# cnc-data-panel.net
KiCad netlist of a schematic drawn in EAGLE
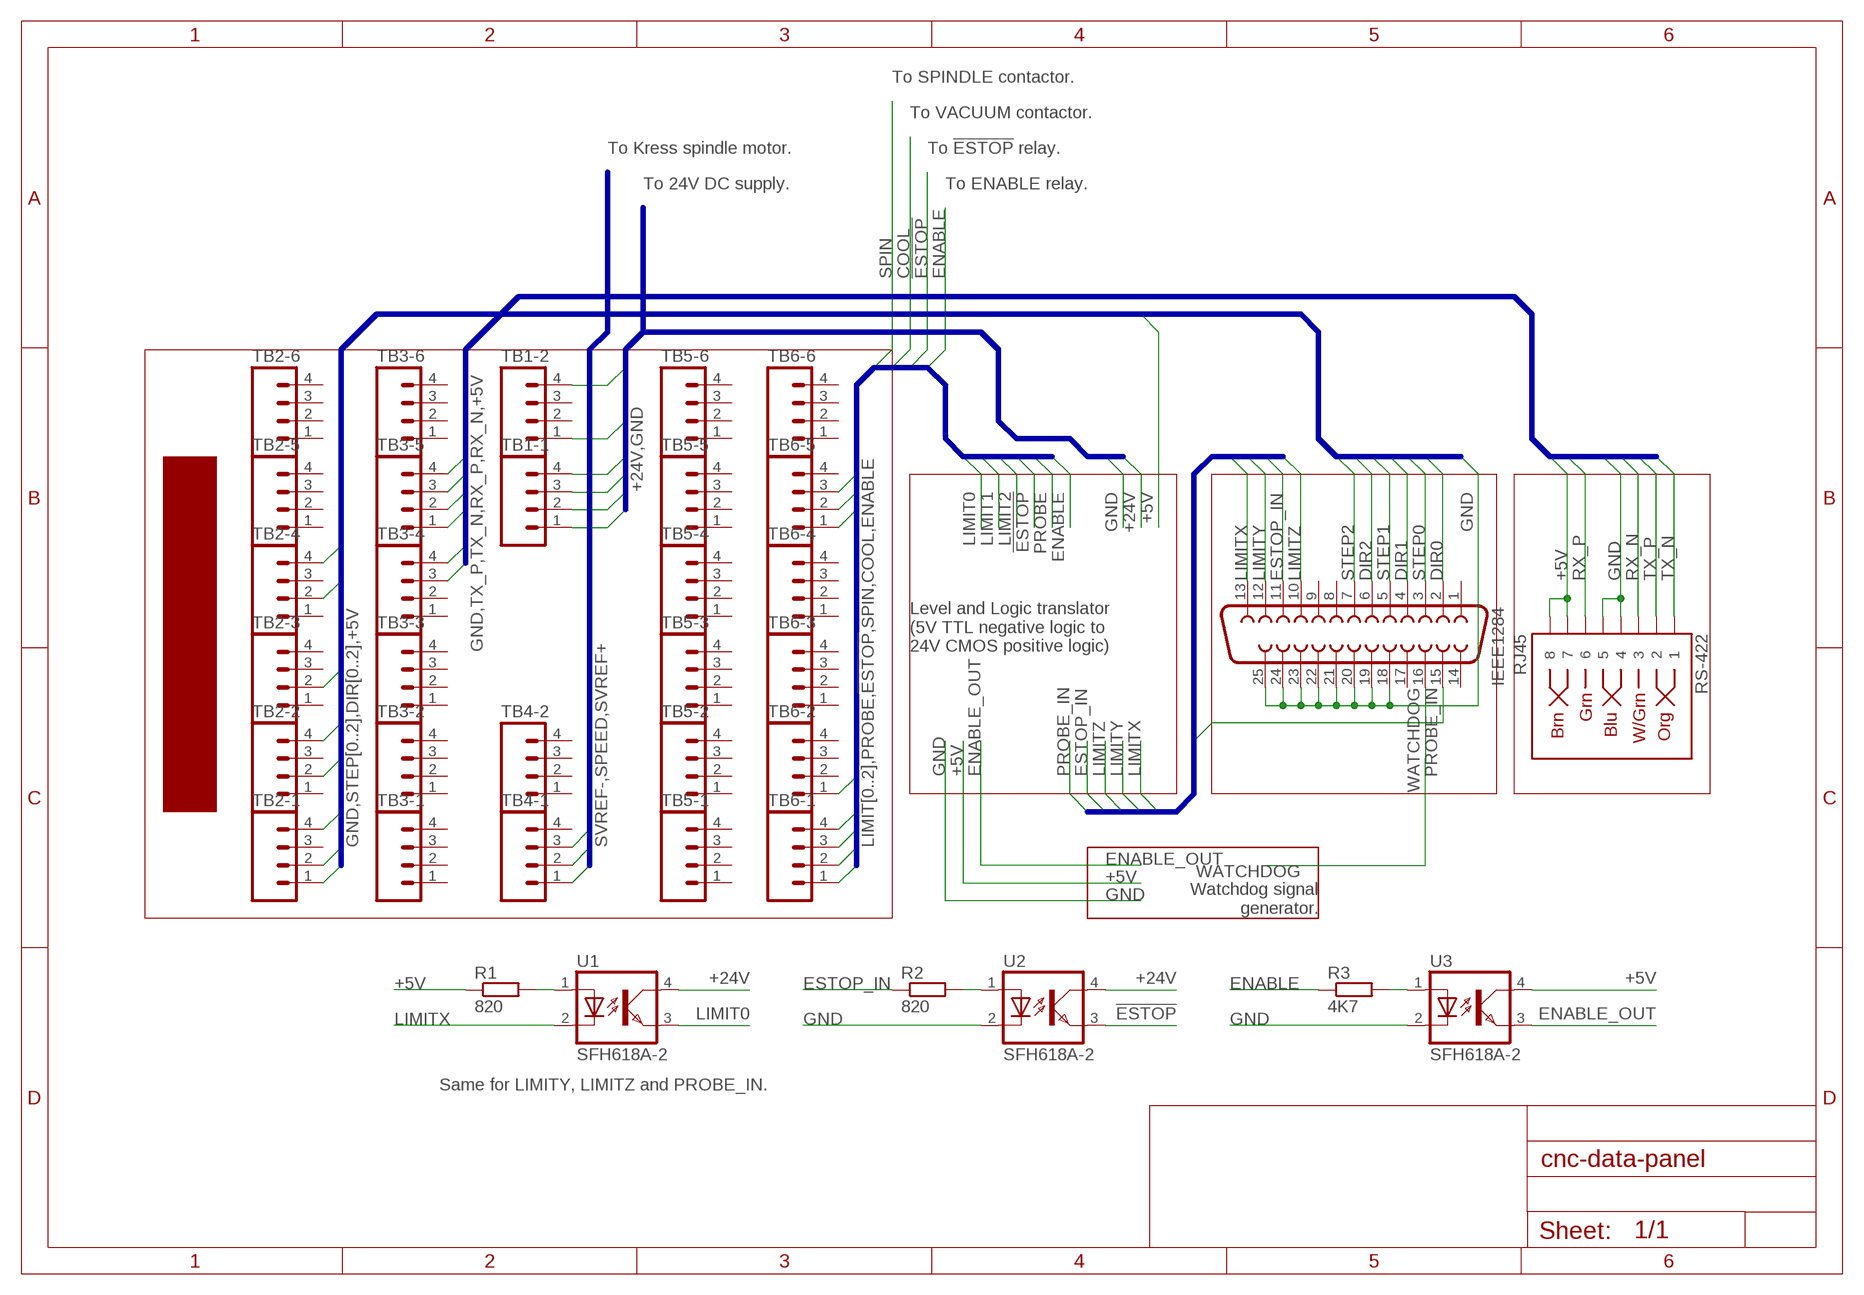
[diagram p0: schematic, sheet 1]

(export (version "E")
  (design (tool "Eeschema 10.0.6"))
  (components
    (comp (ref "IEEE1284")
      (value "F25VP")
      (footprint "eagle-import:F25VP")
      (libsource (lib "eagle-import") (part "F25VP"))
    )
    (comp (ref "R1")
      (value "820")
      (footprint "eagle-import:0204V")
      (libsource (lib "eagle-import") (part "R-EU_0204/2V"))
    )
    (comp (ref "R2")
      (value "820")
      (footprint "eagle-import:0204V")
      (libsource (lib "eagle-import") (part "R-EU_0204/2V"))
    )
    (comp (ref "R3")
      (value "4K7")
      (footprint "eagle-import:0204V")
      (libsource (lib "eagle-import") (part "R-EU_0204/2V"))
    )
    (comp (ref "RS-422")
      (value "RJ45")
      (footprint "eagle-import:RJ45-8")
      (libsource (lib "eagle-import") (part "RJ45-8PTH"))
    )
    (comp (ref "TB1-1")
      (value "M04SCREW")
      (footprint "eagle-import:SCREWTERMINAL-3.5MM-4")
      (libsource (lib "eagle-import") (part "M04SCREW"))
    )
    (comp (ref "TB1-2")
      (value "M04SCREW")
      (footprint "eagle-import:SCREWTERMINAL-3.5MM-4")
      (libsource (lib "eagle-import") (part "M04SCREW"))
    )
    (comp (ref "TB2-1")
      (value "M04SCREW")
      (footprint "eagle-import:SCREWTERMINAL-3.5MM-4")
      (libsource (lib "eagle-import") (part "M04SCREW"))
    )
    (comp (ref "TB2-2")
      (value "M04SCREW")
      (footprint "eagle-import:SCREWTERMINAL-3.5MM-4")
      (libsource (lib "eagle-import") (part "M04SCREW"))
    )
    (comp (ref "TB2-3")
      (value "M04SCREW")
      (footprint "eagle-import:SCREWTERMINAL-3.5MM-4")
      (libsource (lib "eagle-import") (part "M04SCREW"))
    )
    (comp (ref "TB2-4")
      (value "M04SCREW")
      (footprint "eagle-import:SCREWTERMINAL-3.5MM-4")
      (libsource (lib "eagle-import") (part "M04SCREW"))
    )
    (comp (ref "TB2-5")
      (value "M04SCREW")
      (footprint "eagle-import:SCREWTERMINAL-3.5MM-4")
      (libsource (lib "eagle-import") (part "M04SCREW"))
    )
    (comp (ref "TB2-6")
      (value "M04SCREW")
      (footprint "eagle-import:SCREWTERMINAL-3.5MM-4")
      (libsource (lib "eagle-import") (part "M04SCREW"))
    )
    (comp (ref "TB3-1")
      (value "M04SCREW")
      (footprint "eagle-import:SCREWTERMINAL-3.5MM-4")
      (libsource (lib "eagle-import") (part "M04SCREW"))
    )
    (comp (ref "TB3-2")
      (value "M04SCREW")
      (footprint "eagle-import:SCREWTERMINAL-3.5MM-4")
      (libsource (lib "eagle-import") (part "M04SCREW"))
    )
    (comp (ref "TB3-3")
      (value "M04SCREW")
      (footprint "eagle-import:SCREWTERMINAL-3.5MM-4")
      (libsource (lib "eagle-import") (part "M04SCREW"))
    )
    (comp (ref "TB3-4")
      (value "M04SCREW")
      (footprint "eagle-import:SCREWTERMINAL-3.5MM-4")
      (libsource (lib "eagle-import") (part "M04SCREW"))
    )
    (comp (ref "TB3-5")
      (value "M04SCREW")
      (footprint "eagle-import:SCREWTERMINAL-3.5MM-4")
      (libsource (lib "eagle-import") (part "M04SCREW"))
    )
    (comp (ref "TB3-6")
      (value "M04SCREW")
      (footprint "eagle-import:SCREWTERMINAL-3.5MM-4")
      (libsource (lib "eagle-import") (part "M04SCREW"))
    )
    (comp (ref "TB4-1")
      (value "M04SCREW")
      (footprint "eagle-import:SCREWTERMINAL-3.5MM-4")
      (libsource (lib "eagle-import") (part "M04SCREW"))
    )
    (comp (ref "TB4-2")
      (value "M04SCREW")
      (footprint "eagle-import:SCREWTERMINAL-3.5MM-4")
      (libsource (lib "eagle-import") (part "M04SCREW"))
    )
    (comp (ref "TB5-1")
      (value "M04SCREW")
      (footprint "eagle-import:SCREWTERMINAL-3.5MM-4")
      (libsource (lib "eagle-import") (part "M04SCREW"))
    )
    (comp (ref "TB5-2")
      (value "M04SCREW")
      (footprint "eagle-import:SCREWTERMINAL-3.5MM-4")
      (libsource (lib "eagle-import") (part "M04SCREW"))
    )
    (comp (ref "TB5-3")
      (value "M04SCREW")
      (footprint "eagle-import:SCREWTERMINAL-3.5MM-4")
      (libsource (lib "eagle-import") (part "M04SCREW"))
    )
    (comp (ref "TB5-4")
      (value "M04SCREW")
      (footprint "eagle-import:SCREWTERMINAL-3.5MM-4")
      (libsource (lib "eagle-import") (part "M04SCREW"))
    )
    (comp (ref "TB5-5")
      (value "M04SCREW")
      (footprint "eagle-import:SCREWTERMINAL-3.5MM-4")
      (libsource (lib "eagle-import") (part "M04SCREW"))
    )
    (comp (ref "TB5-6")
      (value "M04SCREW")
      (footprint "eagle-import:SCREWTERMINAL-3.5MM-4")
      (libsource (lib "eagle-import") (part "M04SCREW"))
    )
    (comp (ref "TB6-1")
      (value "M04SCREW")
      (footprint "eagle-import:SCREWTERMINAL-3.5MM-4")
      (libsource (lib "eagle-import") (part "M04SCREW"))
    )
    (comp (ref "TB6-2")
      (value "M04SCREW")
      (footprint "eagle-import:SCREWTERMINAL-3.5MM-4")
      (libsource (lib "eagle-import") (part "M04SCREW"))
    )
    (comp (ref "TB6-3")
      (value "M04SCREW")
      (footprint "eagle-import:SCREWTERMINAL-3.5MM-4")
      (libsource (lib "eagle-import") (part "M04SCREW"))
    )
    (comp (ref "TB6-4")
      (value "M04SCREW")
      (footprint "eagle-import:SCREWTERMINAL-3.5MM-4")
      (libsource (lib "eagle-import") (part "M04SCREW"))
    )
    (comp (ref "TB6-5")
      (value "M04SCREW")
      (footprint "eagle-import:SCREWTERMINAL-3.5MM-4")
      (libsource (lib "eagle-import") (part "M04SCREW"))
    )
    (comp (ref "TB6-6")
      (value "M04SCREW")
      (footprint "eagle-import:SCREWTERMINAL-3.5MM-4")
      (libsource (lib "eagle-import") (part "M04SCREW"))
    )
    (comp (ref "U1")
      (value "SFH618A-2")
      (footprint "eagle-import:DIP4")
      (fields (field (name "MF") "VISHAY/TELEFUNKEN"))
      (libsource (lib "eagle-import") (part "SFH618?A-2"))
    )
    (comp (ref "U2")
      (value "SFH618A-2")
      (footprint "eagle-import:DIP4")
      (fields (field (name "MF") "VISHAY/TELEFUNKEN"))
      (libsource (lib "eagle-import") (part "SFH618?A-2"))
    )
    (comp (ref "U3")
      (value "SFH618A-2")
      (footprint "eagle-import:DIP4")
      (fields (field (name "MF") "VISHAY/TELEFUNKEN"))
      (libsource (lib "eagle-import") (part "SFH618?A-2"))
    )
  )
  (nets
    (net (code "4") (name "/+5V") (class "Default")
      (node (ref "R1") (pin "1") (pinfunction "1_1") (pintype "passive"))
      (node (ref "RS-422") (pin "7") (pinfunction "7_7") (pintype "bidirectional"))
      (node (ref "RS-422") (pin "8") (pinfunction "8_8") (pintype "bidirectional"))
      (node (ref "TB2-2") (pin "2") (pinfunction "2_2") (pintype "passive"))
      (node (ref "TB3-5") (pin "4") (pinfunction "4_4") (pintype "passive"))
      (node (ref "U3") (pin "4") (pinfunction "COL_4") (pintype "passive"))
    )
    (net (code "5") (name "/+24V") (class "Default")
      (node (ref "TB1-1") (pin "1") (pinfunction "1_1") (pintype "passive"))
      (node (ref "TB1-1") (pin "2") (pinfunction "2_2") (pintype "passive"))
      (node (ref "TB1-1") (pin "3") (pinfunction "3_3") (pintype "passive"))
      (node (ref "TB1-1") (pin "4") (pinfunction "4_4") (pintype "passive"))
      (node (ref "TB1-2") (pin "1") (pinfunction "1_1") (pintype "passive"))
      (node (ref "U1") (pin "4") (pinfunction "COL_4") (pintype "passive"))
      (node (ref "U2") (pin "4") (pinfunction "COL_4") (pintype "passive"))
    )
    (net (code "6") (name "/COOL") (class "Default")
      (node (ref "TB6-5") (pin "2") (pinfunction "2_2") (pintype "passive"))
    )
    (net (code "7") (name "/DIR0") (class "Default")
      (node (ref "IEEE1284") (pin "2") (pinfunction "2_2") (pintype "passive"))
      (node (ref "TB2-1") (pin "4") (pinfunction "4_4") (pintype "passive"))
    )
    (net (code "8") (name "/DIR1") (class "Default")
      (node (ref "IEEE1284") (pin "4") (pinfunction "4_4") (pintype "passive"))
      (node (ref "TB2-3") (pin "2") (pinfunction "2_2") (pintype "passive"))
    )
    (net (code "9") (name "/DIR2") (class "Default")
      (node (ref "IEEE1284") (pin "6") (pinfunction "6_6") (pintype "passive"))
      (node (ref "TB2-4") (pin "4") (pinfunction "4_4") (pintype "passive"))
    )
    (net (code "10") (name "/ENABLE") (class "Default")
      (node (ref "R3") (pin "1") (pinfunction "1_1") (pintype "passive"))
      (node (ref "TB6-5") (pin "3") (pinfunction "3_3") (pintype "passive"))
    )
    (net (code "11") (name "/ENABLE_OUT") (class "Default")
      (node (ref "U3") (pin "3") (pinfunction "EMIT_3") (pintype "passive"))
    )
    (net (code "12") (name "/ESTOP_IN") (class "Default")
      (node (ref "IEEE1284") (pin "11") (pinfunction "11_11") (pintype "passive"))
      (node (ref "R2") (pin "1") (pinfunction "1_1") (pintype "passive"))
    )
    (net (code "13") (name "/GND") (class "Default")
      (node (ref "IEEE1284") (pin "18") (pinfunction "18_18") (pintype "passive"))
      (node (ref "IEEE1284") (pin "19") (pinfunction "19_19") (pintype "passive"))
      (node (ref "IEEE1284") (pin "20") (pinfunction "20_20") (pintype "passive"))
      (node (ref "IEEE1284") (pin "21") (pinfunction "21_21") (pintype "passive"))
      (node (ref "IEEE1284") (pin "22") (pinfunction "22_22") (pintype "passive"))
      (node (ref "IEEE1284") (pin "23") (pinfunction "23_23") (pintype "passive"))
      (node (ref "IEEE1284") (pin "24") (pinfunction "24_24") (pintype "passive"))
      (node (ref "IEEE1284") (pin "25") (pinfunction "25_25") (pintype "passive"))
      (node (ref "RS-422") (pin "4") (pinfunction "4_4") (pintype "bidirectional"))
      (node (ref "RS-422") (pin "5") (pinfunction "5_5") (pintype "bidirectional"))
      (node (ref "TB1-2") (pin "4") (pinfunction "4_4") (pintype "passive"))
      (node (ref "TB2-1") (pin "1") (pinfunction "1_1") (pintype "passive"))
      (node (ref "TB3-4") (pin "3") (pinfunction "3_3") (pintype "passive"))
      (node (ref "U2") (pin "2") (pinfunction "C_2") (pintype "passive"))
      (node (ref "U3") (pin "2") (pinfunction "C_2") (pintype "passive"))
    )
    (net (code "14") (name "/LIMIT0") (class "Default")
      (node (ref "TB6-1") (pin "1") (pinfunction "1_1") (pintype "passive"))
      (node (ref "U1") (pin "3") (pinfunction "EMIT_3") (pintype "passive"))
    )
    (net (code "15") (name "/LIMIT1") (class "Default")
      (node (ref "TB6-1") (pin "2") (pinfunction "2_2") (pintype "passive"))
    )
    (net (code "16") (name "/LIMIT2") (class "Default")
      (node (ref "TB6-1") (pin "3") (pinfunction "3_3") (pintype "passive"))
    )
    (net (code "17") (name "/LIMITX") (class "Default")
      (node (ref "IEEE1284") (pin "13") (pinfunction "13_13") (pintype "passive"))
      (node (ref "U1") (pin "2") (pinfunction "C_2") (pintype "passive"))
    )
    (net (code "18") (name "/LIMITY") (class "Default")
      (node (ref "IEEE1284") (pin "12") (pinfunction "12_12") (pintype "passive"))
    )
    (net (code "19") (name "/LIMITZ") (class "Default")
      (node (ref "IEEE1284") (pin "10") (pinfunction "10_10") (pintype "passive"))
    )
    (net (code "20") (name "/PROBE") (class "Default")
      (node (ref "TB6-1") (pin "4") (pinfunction "4_4") (pintype "passive"))
    )
    (net (code "21") (name "/PROBE_IN") (class "Default")
      (node (ref "IEEE1284") (pin "15") (pinfunction "15_15") (pintype "passive"))
    )
    (net (code "22") (name "/RX_N") (class "Default")
      (node (ref "RS-422") (pin "3") (pinfunction "3_3") (pintype "bidirectional"))
      (node (ref "TB3-5") (pin "1") (pinfunction "1_1") (pintype "passive"))
    )
    (net (code "23") (name "/RX_P") (class "Default")
      (node (ref "RS-422") (pin "6") (pinfunction "6_6") (pintype "bidirectional"))
      (node (ref "TB3-4") (pin "4") (pinfunction "4_4") (pintype "passive"))
    )
    (net (code "24") (name "/SPIN") (class "Default")
      (node (ref "TB6-5") (pin "1") (pinfunction "1_1") (pintype "passive"))
    )
    (net (code "25") (name "/STEP0") (class "Default")
      (node (ref "IEEE1284") (pin "3") (pinfunction "3_3") (pintype "passive"))
      (node (ref "TB2-1") (pin "2") (pinfunction "2_2") (pintype "passive"))
    )
    (net (code "26") (name "/STEP1") (class "Default")
      (node (ref "IEEE1284") (pin "5") (pinfunction "5_5") (pintype "passive"))
      (node (ref "TB2-2") (pin "4") (pinfunction "4_4") (pintype "passive"))
    )
    (net (code "27") (name "/STEP2") (class "Default")
      (node (ref "IEEE1284") (pin "7") (pinfunction "7_7") (pintype "passive"))
      (node (ref "TB2-4") (pin "2") (pinfunction "2_2") (pintype "passive"))
    )
    (net (code "28") (name "/TX_N") (class "Default")
      (node (ref "RS-422") (pin "1") (pinfunction "1_1") (pintype "bidirectional"))
      (node (ref "TB3-5") (pin "3") (pinfunction "3_3") (pintype "passive"))
    )
    (net (code "29") (name "/TX_P") (class "Default")
      (node (ref "RS-422") (pin "2") (pinfunction "2_2") (pintype "bidirectional"))
      (node (ref "TB3-5") (pin "2") (pinfunction "2_2") (pintype "passive"))
    )
    (net (code "30") (name "/WATCHDOG") (class "Default")
      (node (ref "IEEE1284") (pin "16") (pinfunction "16_16") (pintype "passive"))
    )
    (net (code "36") (name "/~{ESTOP}") (class "Default")
      (node (ref "TB6-2") (pin "1") (pinfunction "1_1") (pintype "passive"))
      (node (ref "U2") (pin "3") (pinfunction "EMIT_3") (pintype "passive"))
    )
    (net (code "37") (name "Net-(U1-A)") (class "Default")
      (node (ref "R1") (pin "2") (pinfunction "2_2") (pintype "passive"))
      (node (ref "U1") (pin "1") (pinfunction "A_1") (pintype "passive"))
    )
    (net (code "38") (name "Net-(U2-A)") (class "Default")
      (node (ref "R2") (pin "2") (pinfunction "2_2") (pintype "passive"))
      (node (ref "U2") (pin "1") (pinfunction "A_1") (pintype "passive"))
    )
    (net (code "39") (name "Net-(U3-A)") (class "Default")
      (node (ref "R3") (pin "2") (pinfunction "2_2") (pintype "passive"))
      (node (ref "U3") (pin "1") (pinfunction "A_1") (pintype "passive"))
    )
    (net (code "40") (name "unconnected-(IEEE1284-Pad1)") (class "Default")
      (node (ref "IEEE1284") (pin "1") (pinfunction "1_1") (pintype "passive"))
    )
    (net (code "41") (name "unconnected-(IEEE1284-Pad8)") (class "Default")
      (node (ref "IEEE1284") (pin "8") (pinfunction "8_8") (pintype "passive"))
    )
    (net (code "42") (name "unconnected-(IEEE1284-Pad9)") (class "Default")
      (node (ref "IEEE1284") (pin "9") (pinfunction "9_9") (pintype "passive"))
    )
    (net (code "43") (name "unconnected-(IEEE1284-Pad14)") (class "Default")
      (node (ref "IEEE1284") (pin "14") (pinfunction "14_14") (pintype "passive"))
    )
    (net (code "44") (name "unconnected-(IEEE1284-Pad17)") (class "Default")
      (node (ref "IEEE1284") (pin "17") (pinfunction "17_17") (pintype "passive"))
    )
    (net (code "45") (name "unconnected-(TB1-2-Pad2)") (class "Default")
      (node (ref "TB1-2") (pin "2") (pinfunction "2_2") (pintype "passive"))
    )
    (net (code "46") (name "unconnected-(TB1-2-Pad3)") (class "Default")
      (node (ref "TB1-2") (pin "3") (pinfunction "3_3") (pintype "passive"))
    )
    (net (code "47") (name "unconnected-(TB2-1-Pad3)") (class "Default")
      (node (ref "TB2-1") (pin "3") (pinfunction "3_3") (pintype "passive"))
    )
    (net (code "48") (name "unconnected-(TB2-2-Pad1)") (class "Default")
      (node (ref "TB2-2") (pin "1") (pinfunction "1_1") (pintype "passive"))
    )
    (net (code "49") (name "unconnected-(TB2-2-Pad3)") (class "Default")
      (node (ref "TB2-2") (pin "3") (pinfunction "3_3") (pintype "passive"))
    )
    (net (code "50") (name "unconnected-(TB2-3-Pad1)") (class "Default")
      (node (ref "TB2-3") (pin "1") (pinfunction "1_1") (pintype "passive"))
    )
    (net (code "51") (name "unconnected-(TB2-3-Pad3)") (class "Default")
      (node (ref "TB2-3") (pin "3") (pinfunction "3_3") (pintype "passive"))
    )
    (net (code "52") (name "unconnected-(TB2-3-Pad4)") (class "Default")
      (node (ref "TB2-3") (pin "4") (pinfunction "4_4") (pintype "passive"))
    )
    (net (code "53") (name "unconnected-(TB2-4-Pad1)") (class "Default")
      (node (ref "TB2-4") (pin "1") (pinfunction "1_1") (pintype "passive"))
    )
    (net (code "54") (name "unconnected-(TB2-4-Pad3)") (class "Default")
      (node (ref "TB2-4") (pin "3") (pinfunction "3_3") (pintype "passive"))
    )
    (net (code "55") (name "unconnected-(TB2-5-Pad1)") (class "Default")
      (node (ref "TB2-5") (pin "1") (pinfunction "1_1") (pintype "passive"))
    )
    (net (code "56") (name "unconnected-(TB2-5-Pad2)") (class "Default")
      (node (ref "TB2-5") (pin "2") (pinfunction "2_2") (pintype "passive"))
    )
    (net (code "57") (name "unconnected-(TB2-5-Pad3)") (class "Default")
      (node (ref "TB2-5") (pin "3") (pinfunction "3_3") (pintype "passive"))
    )
    (net (code "58") (name "unconnected-(TB2-5-Pad4)") (class "Default")
      (node (ref "TB2-5") (pin "4") (pinfunction "4_4") (pintype "passive"))
    )
    (net (code "59") (name "unconnected-(TB2-6-Pad1)") (class "Default")
      (node (ref "TB2-6") (pin "1") (pinfunction "1_1") (pintype "passive"))
    )
    (net (code "60") (name "unconnected-(TB2-6-Pad2)") (class "Default")
      (node (ref "TB2-6") (pin "2") (pinfunction "2_2") (pintype "passive"))
    )
    (net (code "61") (name "unconnected-(TB2-6-Pad3)") (class "Default")
      (node (ref "TB2-6") (pin "3") (pinfunction "3_3") (pintype "passive"))
    )
    (net (code "62") (name "unconnected-(TB2-6-Pad4)") (class "Default")
      (node (ref "TB2-6") (pin "4") (pinfunction "4_4") (pintype "passive"))
    )
    (net (code "63") (name "unconnected-(TB3-1-Pad1)") (class "Default")
      (node (ref "TB3-1") (pin "1") (pinfunction "1_1") (pintype "passive"))
    )
    (net (code "64") (name "unconnected-(TB3-1-Pad2)") (class "Default")
      (node (ref "TB3-1") (pin "2") (pinfunction "2_2") (pintype "passive"))
    )
    (net (code "65") (name "unconnected-(TB3-1-Pad3)") (class "Default")
      (node (ref "TB3-1") (pin "3") (pinfunction "3_3") (pintype "passive"))
    )
    (net (code "66") (name "unconnected-(TB3-1-Pad4)") (class "Default")
      (node (ref "TB3-1") (pin "4") (pinfunction "4_4") (pintype "passive"))
    )
    (net (code "67") (name "unconnected-(TB3-2-Pad1)") (class "Default")
      (node (ref "TB3-2") (pin "1") (pinfunction "1_1") (pintype "passive"))
    )
    (net (code "68") (name "unconnected-(TB3-2-Pad2)") (class "Default")
      (node (ref "TB3-2") (pin "2") (pinfunction "2_2") (pintype "passive"))
    )
    (net (code "69") (name "unconnected-(TB3-2-Pad3)") (class "Default")
      (node (ref "TB3-2") (pin "3") (pinfunction "3_3") (pintype "passive"))
    )
    (net (code "70") (name "unconnected-(TB3-2-Pad4)") (class "Default")
      (node (ref "TB3-2") (pin "4") (pinfunction "4_4") (pintype "passive"))
    )
    (net (code "71") (name "unconnected-(TB3-3-Pad1)") (class "Default")
      (node (ref "TB3-3") (pin "1") (pinfunction "1_1") (pintype "passive"))
    )
    (net (code "72") (name "unconnected-(TB3-3-Pad2)") (class "Default")
      (node (ref "TB3-3") (pin "2") (pinfunction "2_2") (pintype "passive"))
    )
    (net (code "73") (name "unconnected-(TB3-3-Pad3)") (class "Default")
      (node (ref "TB3-3") (pin "3") (pinfunction "3_3") (pintype "passive"))
    )
    (net (code "74") (name "unconnected-(TB3-3-Pad4)") (class "Default")
      (node (ref "TB3-3") (pin "4") (pinfunction "4_4") (pintype "passive"))
    )
    (net (code "75") (name "unconnected-(TB3-4-Pad1)") (class "Default")
      (node (ref "TB3-4") (pin "1") (pinfunction "1_1") (pintype "passive"))
    )
    (net (code "76") (name "unconnected-(TB3-4-Pad2)") (class "Default")
      (node (ref "TB3-4") (pin "2") (pinfunction "2_2") (pintype "passive"))
    )
    (net (code "77") (name "unconnected-(TB3-6-Pad1)") (class "Default")
      (node (ref "TB3-6") (pin "1") (pinfunction "1_1") (pintype "passive"))
    )
    (net (code "78") (name "unconnected-(TB3-6-Pad2)") (class "Default")
      (node (ref "TB3-6") (pin "2") (pinfunction "2_2") (pintype "passive"))
    )
    (net (code "79") (name "unconnected-(TB3-6-Pad3)") (class "Default")
      (node (ref "TB3-6") (pin "3") (pinfunction "3_3") (pintype "passive"))
    )
    (net (code "80") (name "unconnected-(TB3-6-Pad4)") (class "Default")
      (node (ref "TB3-6") (pin "4") (pinfunction "4_4") (pintype "passive"))
    )
    (net (code "81") (name "unconnected-(TB4-1-Pad1)") (class "Default")
      (node (ref "TB4-1") (pin "1") (pinfunction "1_1") (pintype "passive"))
    )
    (net (code "82") (name "unconnected-(TB4-1-Pad2)") (class "Default")
      (node (ref "TB4-1") (pin "2") (pinfunction "2_2") (pintype "passive"))
    )
    (net (code "83") (name "unconnected-(TB4-1-Pad3)") (class "Default")
      (node (ref "TB4-1") (pin "3") (pinfunction "3_3") (pintype "passive"))
    )
    (net (code "84") (name "unconnected-(TB4-1-Pad4)") (class "Default")
      (node (ref "TB4-1") (pin "4") (pinfunction "4_4") (pintype "passive"))
    )
    (net (code "85") (name "unconnected-(TB4-2-Pad1)") (class "Default")
      (node (ref "TB4-2") (pin "1") (pinfunction "1_1") (pintype "passive"))
    )
    (net (code "86") (name "unconnected-(TB4-2-Pad2)") (class "Default")
      (node (ref "TB4-2") (pin "2") (pinfunction "2_2") (pintype "passive"))
    )
    (net (code "87") (name "unconnected-(TB4-2-Pad3)") (class "Default")
      (node (ref "TB4-2") (pin "3") (pinfunction "3_3") (pintype "passive"))
    )
    (net (code "88") (name "unconnected-(TB4-2-Pad4)") (class "Default")
      (node (ref "TB4-2") (pin "4") (pinfunction "4_4") (pintype "passive"))
    )
    (net (code "89") (name "unconnected-(TB5-1-Pad1)") (class "Default")
      (node (ref "TB5-1") (pin "1") (pinfunction "1_1") (pintype "passive"))
    )
    (net (code "90") (name "unconnected-(TB5-1-Pad2)") (class "Default")
      (node (ref "TB5-1") (pin "2") (pinfunction "2_2") (pintype "passive"))
    )
    (net (code "91") (name "unconnected-(TB5-1-Pad3)") (class "Default")
      (node (ref "TB5-1") (pin "3") (pinfunction "3_3") (pintype "passive"))
    )
    (net (code "92") (name "unconnected-(TB5-1-Pad4)") (class "Default")
      (node (ref "TB5-1") (pin "4") (pinfunction "4_4") (pintype "passive"))
    )
    (net (code "93") (name "unconnected-(TB5-2-Pad1)") (class "Default")
      (node (ref "TB5-2") (pin "1") (pinfunction "1_1") (pintype "passive"))
    )
    (net (code "94") (name "unconnected-(TB5-2-Pad2)") (class "Default")
      (node (ref "TB5-2") (pin "2") (pinfunction "2_2") (pintype "passive"))
    )
    (net (code "95") (name "unconnected-(TB5-2-Pad3)") (class "Default")
      (node (ref "TB5-2") (pin "3") (pinfunction "3_3") (pintype "passive"))
    )
    (net (code "96") (name "unconnected-(TB5-2-Pad4)") (class "Default")
      (node (ref "TB5-2") (pin "4") (pinfunction "4_4") (pintype "passive"))
    )
    (net (code "97") (name "unconnected-(TB5-3-Pad1)") (class "Default")
      (node (ref "TB5-3") (pin "1") (pinfunction "1_1") (pintype "passive"))
    )
    (net (code "98") (name "unconnected-(TB5-3-Pad2)") (class "Default")
      (node (ref "TB5-3") (pin "2") (pinfunction "2_2") (pintype "passive"))
    )
    (net (code "99") (name "unconnected-(TB5-3-Pad3)") (class "Default")
      (node (ref "TB5-3") (pin "3") (pinfunction "3_3") (pintype "passive"))
    )
    (net (code "100") (name "unconnected-(TB5-3-Pad4)") (class "Default")
      (node (ref "TB5-3") (pin "4") (pinfunction "4_4") (pintype "passive"))
    )
    (net (code "101") (name "unconnected-(TB5-4-Pad1)") (class "Default")
      (node (ref "TB5-4") (pin "1") (pinfunction "1_1") (pintype "passive"))
    )
    (net (code "102") (name "unconnected-(TB5-4-Pad2)") (class "Default")
      (node (ref "TB5-4") (pin "2") (pinfunction "2_2") (pintype "passive"))
    )
    (net (code "103") (name "unconnected-(TB5-4-Pad3)") (class "Default")
      (node (ref "TB5-4") (pin "3") (pinfunction "3_3") (pintype "passive"))
    )
    (net (code "104") (name "unconnected-(TB5-4-Pad4)") (class "Default")
      (node (ref "TB5-4") (pin "4") (pinfunction "4_4") (pintype "passive"))
    )
    (net (code "105") (name "unconnected-(TB5-5-Pad1)") (class "Default")
      (node (ref "TB5-5") (pin "1") (pinfunction "1_1") (pintype "passive"))
    )
    (net (code "106") (name "unconnected-(TB5-5-Pad2)") (class "Default")
      (node (ref "TB5-5") (pin "2") (pinfunction "2_2") (pintype "passive"))
    )
    (net (code "107") (name "unconnected-(TB5-5-Pad3)") (class "Default")
      (node (ref "TB5-5") (pin "3") (pinfunction "3_3") (pintype "passive"))
    )
    (net (code "108") (name "unconnected-(TB5-5-Pad4)") (class "Default")
      (node (ref "TB5-5") (pin "4") (pinfunction "4_4") (pintype "passive"))
    )
    (net (code "109") (name "unconnected-(TB5-6-Pad1)") (class "Default")
      (node (ref "TB5-6") (pin "1") (pinfunction "1_1") (pintype "passive"))
    )
    (net (code "110") (name "unconnected-(TB5-6-Pad2)") (class "Default")
      (node (ref "TB5-6") (pin "2") (pinfunction "2_2") (pintype "passive"))
    )
    (net (code "111") (name "unconnected-(TB5-6-Pad3)") (class "Default")
      (node (ref "TB5-6") (pin "3") (pinfunction "3_3") (pintype "passive"))
    )
    (net (code "112") (name "unconnected-(TB5-6-Pad4)") (class "Default")
      (node (ref "TB5-6") (pin "4") (pinfunction "4_4") (pintype "passive"))
    )
    (net (code "113") (name "unconnected-(TB6-2-Pad2)") (class "Default")
      (node (ref "TB6-2") (pin "2") (pinfunction "2_2") (pintype "passive"))
    )
    (net (code "114") (name "unconnected-(TB6-2-Pad3)") (class "Default")
      (node (ref "TB6-2") (pin "3") (pinfunction "3_3") (pintype "passive"))
    )
    (net (code "115") (name "unconnected-(TB6-2-Pad4)") (class "Default")
      (node (ref "TB6-2") (pin "4") (pinfunction "4_4") (pintype "passive"))
    )
    (net (code "116") (name "unconnected-(TB6-3-Pad1)") (class "Default")
      (node (ref "TB6-3") (pin "1") (pinfunction "1_1") (pintype "passive"))
    )
    (net (code "117") (name "unconnected-(TB6-3-Pad2)") (class "Default")
      (node (ref "TB6-3") (pin "2") (pinfunction "2_2") (pintype "passive"))
    )
    (net (code "118") (name "unconnected-(TB6-3-Pad3)") (class "Default")
      (node (ref "TB6-3") (pin "3") (pinfunction "3_3") (pintype "passive"))
    )
    (net (code "119") (name "unconnected-(TB6-3-Pad4)") (class "Default")
      (node (ref "TB6-3") (pin "4") (pinfunction "4_4") (pintype "passive"))
    )
    (net (code "120") (name "unconnected-(TB6-4-Pad1)") (class "Default")
      (node (ref "TB6-4") (pin "1") (pinfunction "1_1") (pintype "passive"))
    )
    (net (code "121") (name "unconnected-(TB6-4-Pad2)") (class "Default")
      (node (ref "TB6-4") (pin "2") (pinfunction "2_2") (pintype "passive"))
    )
    (net (code "122") (name "unconnected-(TB6-4-Pad3)") (class "Default")
      (node (ref "TB6-4") (pin "3") (pinfunction "3_3") (pintype "passive"))
    )
    (net (code "123") (name "unconnected-(TB6-4-Pad4)") (class "Default")
      (node (ref "TB6-4") (pin "4") (pinfunction "4_4") (pintype "passive"))
    )
    (net (code "124") (name "unconnected-(TB6-5-Pad4)") (class "Default")
      (node (ref "TB6-5") (pin "4") (pinfunction "4_4") (pintype "passive"))
    )
    (net (code "125") (name "unconnected-(TB6-6-Pad1)") (class "Default")
      (node (ref "TB6-6") (pin "1") (pinfunction "1_1") (pintype "passive"))
    )
    (net (code "126") (name "unconnected-(TB6-6-Pad2)") (class "Default")
      (node (ref "TB6-6") (pin "2") (pinfunction "2_2") (pintype "passive"))
    )
    (net (code "127") (name "unconnected-(TB6-6-Pad3)") (class "Default")
      (node (ref "TB6-6") (pin "3") (pinfunction "3_3") (pintype "passive"))
    )
    (net (code "128") (name "unconnected-(TB6-6-Pad4)") (class "Default")
      (node (ref "TB6-6") (pin "4") (pinfunction "4_4") (pintype "passive"))
    )
  )
)
